# HolderDog.net
KiCad netlist of a schematic drawn in Altium Designer
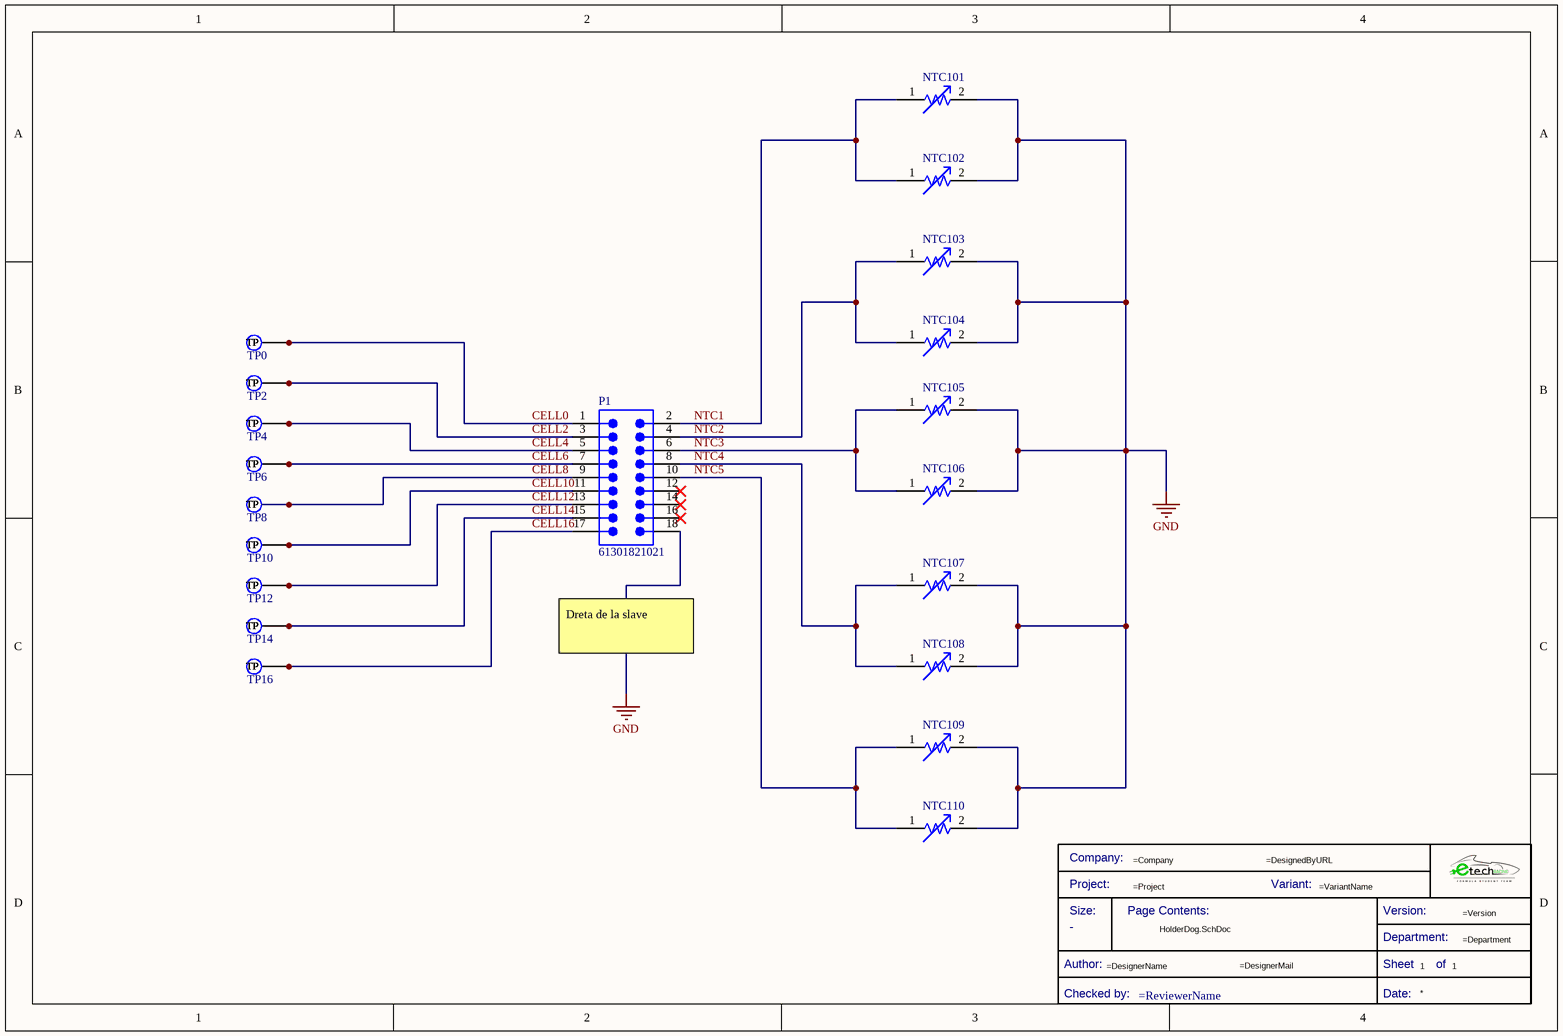
[diagram p0: HolderDog.SchDoc]

(export (version "E")
  (design (tool "Eeschema 10.0.6"))
  (components
    (comp (ref "*")
      (value "Title Block_template")
      (description "Standard Title Block")
      (fields
        (field (name "SIZE") "-")
        (field (name ".CREATOR") "GP")
        (field (name ".PCBCHECK") "GP")
        (field (name ".SCHCHECK") "GP")
      )
      (libsource (lib "e-Tech_Racing") (part "Title Block_template"))
    )
    (comp (ref "NTC101")
      (value "NTC SMD 0805")
      (footprint "RESC2012X10N")
      (description "NTC 0805 package 10kR")
      (libsource (lib "EMEA- E-Tech Racing- I'Escola d'Enginyeria de Barcelona Est") (part "0805"))
    )
    (comp (ref "NTC102")
      (value "NTC SMD 0805")
      (footprint "RESC2012X10N")
      (description "NTC 0805 package 10kR")
      (libsource (lib "EMEA- E-Tech Racing- I'Escola d'Enginyeria de Barcelona Est") (part "0805"))
    )
    (comp (ref "NTC103")
      (value "NTC SMD 0805")
      (footprint "RESC2012X10N")
      (description "NTC 0805 package 10kR")
      (libsource (lib "EMEA- E-Tech Racing- I'Escola d'Enginyeria de Barcelona Est") (part "0805"))
    )
    (comp (ref "NTC104")
      (value "NTC SMD 0805")
      (footprint "RESC2012X10N")
      (description "NTC 0805 package 10kR")
      (libsource (lib "EMEA- E-Tech Racing- I'Escola d'Enginyeria de Barcelona Est") (part "0805"))
    )
    (comp (ref "NTC105")
      (value "NTC SMD 0805")
      (footprint "RESC2012X10N")
      (description "NTC 0805 package 10kR")
      (libsource (lib "EMEA- E-Tech Racing- I'Escola d'Enginyeria de Barcelona Est") (part "0805"))
    )
    (comp (ref "NTC106")
      (value "NTC SMD 0805")
      (footprint "RESC2012X10N")
      (description "NTC 0805 package 10kR")
      (libsource (lib "EMEA- E-Tech Racing- I'Escola d'Enginyeria de Barcelona Est") (part "0805"))
    )
    (comp (ref "NTC107")
      (value "NTC SMD 0805")
      (footprint "RESC2012X10N")
      (description "NTC 0805 package 10kR")
      (libsource (lib "EMEA- E-Tech Racing- I'Escola d'Enginyeria de Barcelona Est") (part "0805"))
    )
    (comp (ref "NTC108")
      (value "NTC SMD 0805")
      (footprint "RESC2012X10N")
      (description "NTC 0805 package 10kR")
      (libsource (lib "EMEA- E-Tech Racing- I'Escola d'Enginyeria de Barcelona Est") (part "0805"))
    )
    (comp (ref "NTC109")
      (value "NTC SMD 0805")
      (footprint "RESC2012X10N")
      (description "NTC 0805 package 10kR")
      (libsource (lib "EMEA- E-Tech Racing- I'Escola d'Enginyeria de Barcelona Est") (part "0805"))
    )
    (comp (ref "NTC110")
      (value "NTC SMD 0805")
      (footprint "RESC2012X10N")
      (description "NTC 0805 package 10kR")
      (libsource (lib "EMEA- E-Tech Racing- I'Escola d'Enginyeria de Barcelona Est") (part "0805"))
    )
    (comp (ref "P1")
      (value "61301821021")
      (footprint "61301821021")
      (libsource (lib "EMEA- E-Tech Racing- I'Escola d'Enginyeria de Barcelona Est") (part "Header_Male_2R_18P"))
    )
    (comp (ref "TP0")
      (value "Test Point")
      (footprint "TESTPOINT_WIDE")
      (description "TestPoint 5x5mm")
      (libsource (lib "e-Tech_Racing") (part "TestPoint_Wide"))
    )
    (comp (ref "TP2")
      (value "Test Point")
      (footprint "TESTPOINT_WIDE")
      (description "TestPoint 5x5mm")
      (libsource (lib "e-Tech_Racing") (part "TestPoint_Wide"))
    )
    (comp (ref "TP4")
      (value "Test Point")
      (footprint "TESTPOINT_WIDE")
      (description "TestPoint 5x5mm")
      (libsource (lib "e-Tech_Racing") (part "TestPoint_Wide"))
    )
    (comp (ref "TP6")
      (value "Test Point")
      (footprint "TESTPOINT_WIDE")
      (description "TestPoint 5x5mm")
      (libsource (lib "e-Tech_Racing") (part "TestPoint_Wide"))
    )
    (comp (ref "TP8")
      (value "Test Point")
      (footprint "TESTPOINT_WIDE")
      (description "TestPoint 5x5mm")
      (libsource (lib "e-Tech_Racing") (part "TestPoint_Wide"))
    )
    (comp (ref "TP10")
      (value "Test Point")
      (footprint "TESTPOINT_WIDE")
      (description "TestPoint 5x5mm")
      (libsource (lib "e-Tech_Racing") (part "TestPoint_Wide"))
    )
    (comp (ref "TP12")
      (value "Test Point")
      (footprint "TESTPOINT_WIDE")
      (description "TestPoint 5x5mm")
      (libsource (lib "e-Tech_Racing") (part "TestPoint_Wide"))
    )
    (comp (ref "TP14")
      (value "Test Point")
      (footprint "TESTPOINT_WIDE")
      (description "TestPoint 5x5mm")
      (libsource (lib "e-Tech_Racing") (part "TestPoint_Wide"))
    )
    (comp (ref "TP16")
      (value "Test Point")
      (footprint "TESTPOINT_WIDE")
      (description "TestPoint 5x5mm")
      (libsource (lib "e-Tech_Racing") (part "TestPoint_Wide"))
    )
  )
  (nets
    (net (code "1") (name "/CELL0") (class "Default")
      (node (ref "P1") (pin "1") (pinfunction "1_1") (pintype "passive"))
      (node (ref "TP0") (pin "1") (pinfunction "TP_1") (pintype "passive"))
    )
    (net (code "2") (name "/CELL2") (class "Default")
      (node (ref "P1") (pin "3") (pinfunction "3_3") (pintype "passive"))
      (node (ref "TP2") (pin "1") (pinfunction "TP_1") (pintype "passive"))
    )
    (net (code "3") (name "/CELL4") (class "Default")
      (node (ref "P1") (pin "5") (pinfunction "5_5") (pintype "passive"))
      (node (ref "TP4") (pin "1") (pinfunction "TP_1") (pintype "passive"))
    )
    (net (code "4") (name "/CELL6") (class "Default")
      (node (ref "P1") (pin "7") (pinfunction "7_7") (pintype "passive"))
      (node (ref "TP6") (pin "1") (pinfunction "TP_1") (pintype "passive"))
    )
    (net (code "5") (name "/CELL8") (class "Default")
      (node (ref "P1") (pin "9") (pinfunction "9_9") (pintype "passive"))
      (node (ref "TP8") (pin "1") (pinfunction "TP_1") (pintype "passive"))
    )
    (net (code "6") (name "/CELL10") (class "Default")
      (node (ref "P1") (pin "11") (pinfunction "11_11") (pintype "passive"))
      (node (ref "TP10") (pin "1") (pinfunction "TP_1") (pintype "passive"))
    )
    (net (code "7") (name "/CELL12") (class "Default")
      (node (ref "P1") (pin "13") (pinfunction "13_13") (pintype "passive"))
      (node (ref "TP12") (pin "1") (pinfunction "TP_1") (pintype "passive"))
    )
    (net (code "8") (name "/CELL14") (class "Default")
      (node (ref "P1") (pin "15") (pinfunction "15_15") (pintype "passive"))
      (node (ref "TP14") (pin "1") (pinfunction "TP_1") (pintype "passive"))
    )
    (net (code "9") (name "/CELL16") (class "Default")
      (node (ref "P1") (pin "17") (pinfunction "17_17") (pintype "passive"))
      (node (ref "TP16") (pin "1") (pinfunction "TP_1") (pintype "passive"))
    )
    (net (code "10") (name "/NTC1") (class "Default")
      (node (ref "NTC101") (pin "1") (pinfunction "1_1") (pintype "passive"))
      (node (ref "NTC102") (pin "1") (pinfunction "1_1") (pintype "passive"))
      (node (ref "P1") (pin "2") (pinfunction "2_2") (pintype "passive"))
    )
    (net (code "11") (name "/NTC2") (class "Default")
      (node (ref "NTC103") (pin "1") (pinfunction "1_1") (pintype "passive"))
      (node (ref "NTC104") (pin "1") (pinfunction "1_1") (pintype "passive"))
      (node (ref "P1") (pin "4") (pinfunction "4_4") (pintype "passive"))
    )
    (net (code "12") (name "/NTC3") (class "Default")
      (node (ref "NTC105") (pin "1") (pinfunction "1_1") (pintype "passive"))
      (node (ref "NTC106") (pin "1") (pinfunction "1_1") (pintype "passive"))
      (node (ref "P1") (pin "6") (pinfunction "6_6") (pintype "passive"))
    )
    (net (code "13") (name "/NTC4") (class "Default")
      (node (ref "NTC107") (pin "1") (pinfunction "1_1") (pintype "passive"))
      (node (ref "NTC108") (pin "1") (pinfunction "1_1") (pintype "passive"))
      (node (ref "P1") (pin "8") (pinfunction "8_8") (pintype "passive"))
    )
    (net (code "14") (name "/NTC5") (class "Default")
      (node (ref "NTC109") (pin "1") (pinfunction "1_1") (pintype "passive"))
      (node (ref "NTC110") (pin "1") (pinfunction "1_1") (pintype "passive"))
      (node (ref "P1") (pin "10") (pinfunction "10_10") (pintype "passive"))
    )
    (net (code "15") (name "GND") (class "Default")
      (node (ref "NTC101") (pin "2") (pinfunction "2_2") (pintype "passive"))
      (node (ref "NTC102") (pin "2") (pinfunction "2_2") (pintype "passive"))
      (node (ref "NTC103") (pin "2") (pinfunction "2_2") (pintype "passive"))
      (node (ref "NTC104") (pin "2") (pinfunction "2_2") (pintype "passive"))
      (node (ref "NTC105") (pin "2") (pinfunction "2_2") (pintype "passive"))
      (node (ref "NTC106") (pin "2") (pinfunction "2_2") (pintype "passive"))
      (node (ref "NTC107") (pin "2") (pinfunction "2_2") (pintype "passive"))
      (node (ref "NTC108") (pin "2") (pinfunction "2_2") (pintype "passive"))
      (node (ref "NTC109") (pin "2") (pinfunction "2_2") (pintype "passive"))
      (node (ref "NTC110") (pin "2") (pinfunction "2_2") (pintype "passive"))
      (node (ref "P1") (pin "18") (pinfunction "18_18") (pintype "passive"))
    )
    (net (code "16") (name "unconnected-(P1-Pad12)") (class "Default")
      (node (ref "P1") (pin "12") (pinfunction "12_12") (pintype "passive+no_connect"))
    )
    (net (code "17") (name "unconnected-(P1-Pad14)") (class "Default")
      (node (ref "P1") (pin "14") (pinfunction "14_14") (pintype "passive+no_connect"))
    )
    (net (code "18") (name "unconnected-(P1-Pad16)") (class "Default")
      (node (ref "P1") (pin "16") (pinfunction "16_16") (pintype "passive+no_connect"))
    )
  )
)
